# High_Current_Supply.net
KiCad netlist of a schematic drawn in EAGLE
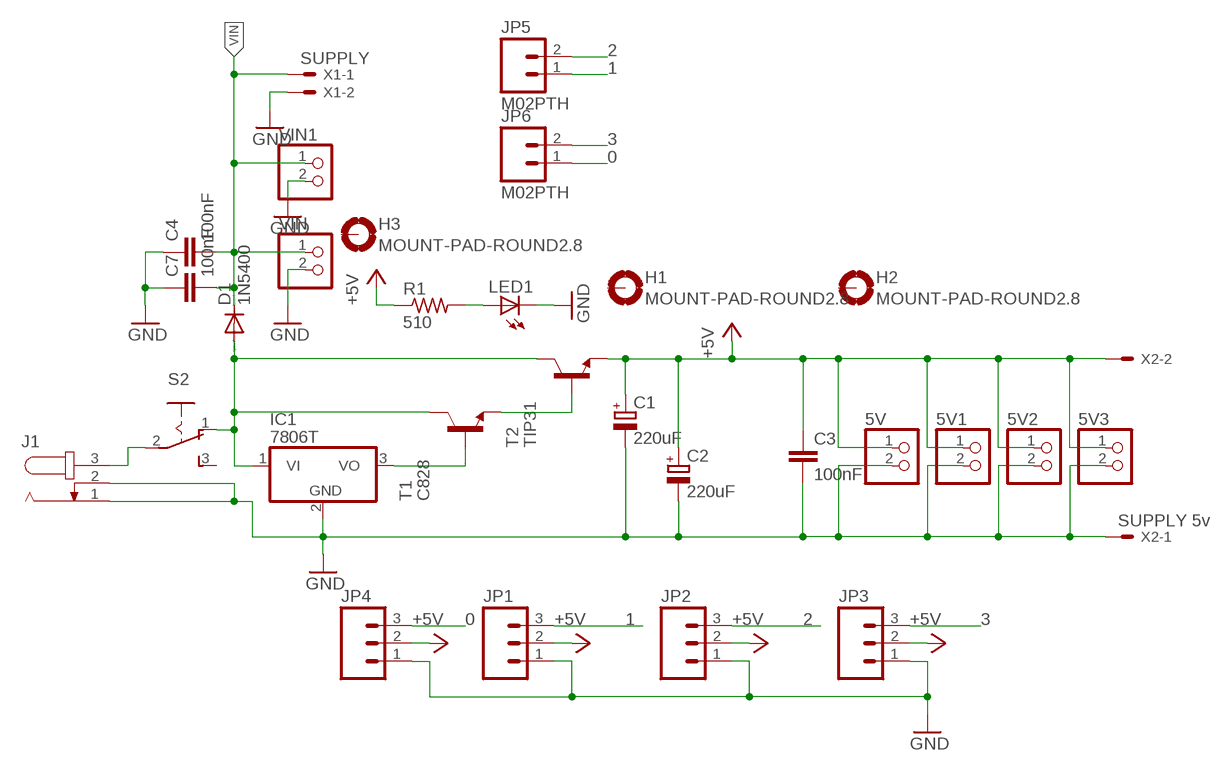
[diagram p0: schematic, sheet 1]

(export (version "E")
  (design (tool "Eeschema 10.0.6"))
  (components
    (comp (ref "5V")
      (value "PINHD-1X2")
      (footprint "eagle-import:1X02")
      (libsource (lib "eagle-import") (part "PINHD-1X2"))
    )
    (comp (ref "5V1")
      (value "PINHD-1X2")
      (footprint "eagle-import:1X02")
      (libsource (lib "eagle-import") (part "PINHD-1X2"))
    )
    (comp (ref "5V2")
      (value "PINHD-1X2")
      (footprint "eagle-import:1X02")
      (libsource (lib "eagle-import") (part "PINHD-1X2"))
    )
    (comp (ref "5V3")
      (value "PINHD-1X2")
      (footprint "eagle-import:1X02")
      (libsource (lib "eagle-import") (part "PINHD-1X2"))
    )
    (comp (ref "C1")
      (value "220uF")
      (footprint "eagle-import:E2,5-7")
      (libsource (lib "eagle-import") (part "CPOL-EUE2.5-7"))
    )
    (comp (ref "C2")
      (value "220uF")
      (footprint "eagle-import:E2,5-7")
      (libsource (lib "eagle-import") (part "CPOL-EUE2.5-7"))
    )
    (comp (ref "C3")
      (value "100nF")
      (footprint "eagle-import:C5B3")
      (libsource (lib "eagle-import") (part "C5/3"))
    )
    (comp (ref "C4")
      (value "100nF")
      (footprint "eagle-import:C5B3")
      (libsource (lib "eagle-import") (part "C5/3"))
    )
    (comp (ref "C7")
      (value "100nF")
      (footprint "eagle-import:C5B3")
      (libsource (lib "eagle-import") (part "C5/3"))
    )
    (comp (ref "D1")
      (value "1N5400")
      (footprint "eagle-import:DO201-15")
      (libsource (lib "eagle-import") (part "1N5400"))
    )
    (comp (ref "H1")
      (value "MOUNT-PAD-ROUND2.8")
      (footprint "eagle-import:2,8-PAD")
      (libsource (lib "eagle-import") (part "MOUNT-PAD-ROUND2.8"))
    )
    (comp (ref "H2")
      (value "MOUNT-PAD-ROUND2.8")
      (footprint "eagle-import:2,8-PAD")
      (libsource (lib "eagle-import") (part "MOUNT-PAD-ROUND2.8"))
    )
    (comp (ref "H3")
      (value "MOUNT-PAD-ROUND2.8")
      (footprint "eagle-import:2,8-PAD")
      (libsource (lib "eagle-import") (part "MOUNT-PAD-ROUND2.8"))
    )
    (comp (ref "IC1")
      (value "7806T")
      (footprint "eagle-import:TO220H")
      (libsource (lib "eagle-import") (part "78T06"))
    )
    (comp (ref "J1")
      (value "JACK-PLUG1")
      (footprint "eagle-import:SPC4078")
      (libsource (lib "eagle-import") (part "JACK-PLUG1"))
    )
    (comp (ref "JP1")
      (value "M03PTH")
      (footprint "eagle-import:1X03")
      (libsource (lib "eagle-import") (part "M03PTH"))
    )
    (comp (ref "JP2")
      (value "M03PTH")
      (footprint "eagle-import:1X03")
      (libsource (lib "eagle-import") (part "M03PTH"))
    )
    (comp (ref "JP3")
      (value "M03PTH")
      (footprint "eagle-import:1X03")
      (libsource (lib "eagle-import") (part "M03PTH"))
    )
    (comp (ref "JP4")
      (value "M03PTH")
      (footprint "eagle-import:1X03")
      (libsource (lib "eagle-import") (part "M03PTH"))
    )
    (comp (ref "JP5")
      (value "M02PTH")
      (footprint "eagle-import:1X02")
      (libsource (lib "eagle-import") (part "M02PTH"))
    )
    (comp (ref "JP6")
      (value "M02PTH")
      (footprint "eagle-import:1X02")
      (libsource (lib "eagle-import") (part "M02PTH"))
    )
    (comp (ref "LED1")
      (value "LED3MM")
      (footprint "eagle-import:LED3MM")
      (libsource (lib "eagle-import") (part "LED3MM"))
    )
    (comp (ref "R1")
      (value "510")
      (footprint "eagle-import:R0603")
      (libsource (lib "eagle-import") (part "R-US_R0603"))
    )
    (comp (ref "S2")
      (value "255SB")
      (footprint "eagle-import:255SB")
      (libsource (lib "eagle-import") (part "255SB"))
    )
    (comp (ref "T1")
      (value "C828")
      (footprint "eagle-import:TO92-ECB")
      (libsource (lib "eagle-import") (part "2SC945"))
    )
    (comp (ref "T2")
      (value "TIP31")
      (footprint "eagle-import:TO220")
      (libsource (lib "eagle-import") (part "TIP31"))
    )
    (comp (ref "VIN")
      (value "PINHD-1X2")
      (footprint "eagle-import:1X02")
      (libsource (lib "eagle-import") (part "PINHD-1X2"))
    )
    (comp (ref "VIN1")
      (value "PINHD-1X2")
      (footprint "eagle-import:1X02")
      (libsource (lib "eagle-import") (part "PINHD-1X2"))
    )
    (comp (ref "X1")
      (value "SUPPLY")
      (footprint "eagle-import:JST-XH-02-PACKAGE-LONG-PAD")
      (libsource (lib "eagle-import") (part "JST-XH-02-PIN-LONG-PAD"))
    )
    (comp (ref "X2")
      (value "SUPPLY 5v")
      (footprint "eagle-import:JST-XH-02-PACKAGE-LONG-PAD")
      (libsource (lib "eagle-import") (part "JST-XH-02-PIN-LONG-PAD"))
    )
  )
  (nets
    (net (code "1") (name "+5V") (class "Default")
      (node (ref "5V") (pin "1") (pinfunction "1_1") (pintype "passive"))
      (node (ref "5V1") (pin "1") (pinfunction "1_1") (pintype "passive"))
      (node (ref "5V2") (pin "1") (pinfunction "1_1") (pintype "passive"))
      (node (ref "5V3") (pin "1") (pinfunction "1_1") (pintype "passive"))
      (node (ref "C1") (pin "+") (pinfunction "+_+") (pintype "passive"))
      (node (ref "C2") (pin "+") (pinfunction "+_+") (pintype "passive"))
      (node (ref "C3") (pin "1") (pinfunction "1_1") (pintype "passive"))
      (node (ref "JP1") (pin "2") (pinfunction "2_2") (pintype "passive"))
      (node (ref "JP2") (pin "2") (pinfunction "2_2") (pintype "passive"))
      (node (ref "JP3") (pin "2") (pinfunction "2_2") (pintype "passive"))
      (node (ref "JP4") (pin "2") (pinfunction "2_2") (pintype "passive"))
      (node (ref "R1") (pin "1") (pinfunction "1_1") (pintype "passive"))
      (node (ref "T2") (pin "3") (pinfunction "E_3") (pintype "passive"))
      (node (ref "X2") (pin "2") (pinfunction "S_2") (pintype "passive"))
    )
    (net (code "2") (name "/0") (class "Default")
      (node (ref "JP4") (pin "3") (pinfunction "3_3") (pintype "passive"))
      (node (ref "JP6") (pin "1") (pinfunction "1_1") (pintype "passive"))
    )
    (net (code "3") (name "/1") (class "Default")
      (node (ref "JP1") (pin "3") (pinfunction "3_3") (pintype "passive"))
      (node (ref "JP5") (pin "1") (pinfunction "1_1") (pintype "passive"))
    )
    (net (code "4") (name "/2") (class "Default")
      (node (ref "JP2") (pin "3") (pinfunction "3_3") (pintype "passive"))
      (node (ref "JP5") (pin "2") (pinfunction "2_2") (pintype "passive"))
    )
    (net (code "5") (name "/3") (class "Default")
      (node (ref "JP3") (pin "3") (pinfunction "3_3") (pintype "passive"))
      (node (ref "JP6") (pin "2") (pinfunction "2_2") (pintype "passive"))
    )
    (net (code "6") (name "GND") (class "Default")
      (node (ref "5V") (pin "2") (pinfunction "2_2") (pintype "passive"))
      (node (ref "5V1") (pin "2") (pinfunction "2_2") (pintype "passive"))
      (node (ref "5V2") (pin "2") (pinfunction "2_2") (pintype "passive"))
      (node (ref "5V3") (pin "2") (pinfunction "2_2") (pintype "passive"))
      (node (ref "C1") (pin "-") (pinfunction "-_-") (pintype "passive"))
      (node (ref "C2") (pin "-") (pinfunction "-_-") (pintype "passive"))
      (node (ref "C3") (pin "2") (pinfunction "2_2") (pintype "passive"))
      (node (ref "C4") (pin "1") (pinfunction "1_1") (pintype "passive"))
      (node (ref "C7") (pin "1") (pinfunction "1_1") (pintype "passive"))
      (node (ref "IC1") (pin "2") (pinfunction "GND_2") (pintype "passive"))
      (node (ref "J1") (pin "1") (pinfunction "1_1") (pintype "passive"))
      (node (ref "J1") (pin "2") (pinfunction "2_2") (pintype "passive"))
      (node (ref "JP1") (pin "1") (pinfunction "1_1") (pintype "passive"))
      (node (ref "JP2") (pin "1") (pinfunction "1_1") (pintype "passive"))
      (node (ref "JP3") (pin "1") (pinfunction "1_1") (pintype "passive"))
      (node (ref "JP4") (pin "1") (pinfunction "1_1") (pintype "passive"))
      (node (ref "LED1") (pin "K") (pinfunction "C_K") (pintype "passive"))
      (node (ref "VIN") (pin "2") (pinfunction "2_2") (pintype "passive"))
      (node (ref "VIN1") (pin "2") (pinfunction "2_2") (pintype "passive"))
      (node (ref "X1") (pin "2") (pinfunction "S_2") (pintype "passive"))
      (node (ref "X2") (pin "1") (pinfunction "S_1") (pintype "passive"))
    )
    (net (code "7") (name "Net-(IC1-VI)") (class "Default")
      (node (ref "D1") (pin "A") (pinfunction "A_A") (pintype "passive"))
      (node (ref "IC1") (pin "1") (pinfunction "VI_1") (pintype "input"))
      (node (ref "S2") (pin "1") (pinfunction "O_1") (pintype "passive"))
      (node (ref "T1") (pin "C") (pinfunction "C_C") (pintype "passive"))
      (node (ref "T2") (pin "2") (pinfunction "C_2") (pintype "passive"))
    )
    (net (code "8") (name "Net-(IC1-VO)") (class "Default")
      (node (ref "IC1") (pin "3") (pinfunction "VO_3") (pintype "passive"))
      (node (ref "T1") (pin "B") (pinfunction "B_B") (pintype "passive"))
    )
    (net (code "9") (name "Net-(LED1-PadA)") (class "Default")
      (node (ref "LED1") (pin "A") (pinfunction "A_A") (pintype "passive"))
      (node (ref "R1") (pin "2") (pinfunction "2_2") (pintype "passive"))
    )
    (net (code "10") (name "Net-(S2-P)") (class "Default")
      (node (ref "J1") (pin "3") (pinfunction "3_3") (pintype "passive"))
      (node (ref "S2") (pin "2") (pinfunction "P_2") (pintype "passive"))
    )
    (net (code "11") (name "Net-(T2-B)") (class "Default")
      (node (ref "T1") (pin "E") (pinfunction "E_E") (pintype "passive"))
      (node (ref "T2") (pin "1") (pinfunction "B_1") (pintype "passive"))
    )
    (net (code "12") (name "VIN") (class "Default")
      (node (ref "C4") (pin "2") (pinfunction "2_2") (pintype "passive"))
      (node (ref "C7") (pin "2") (pinfunction "2_2") (pintype "passive"))
      (node (ref "D1") (pin "C") (pinfunction "C_C") (pintype "passive"))
      (node (ref "VIN") (pin "1") (pinfunction "1_1") (pintype "passive"))
      (node (ref "VIN1") (pin "1") (pinfunction "1_1") (pintype "passive"))
      (node (ref "X1") (pin "1") (pinfunction "S_1") (pintype "passive"))
    )
    (net (code "13") (name "unconnected-(H1-MOUNT-PadB2,8)") (class "Default")
      (node (ref "H1") (pin "B2,8") (pinfunction "MOUNT_B2,8") (pintype "passive"))
    )
    (net (code "14") (name "unconnected-(H2-MOUNT-PadB2,8)") (class "Default")
      (node (ref "H2") (pin "B2,8") (pinfunction "MOUNT_B2,8") (pintype "passive"))
    )
    (net (code "15") (name "unconnected-(H3-MOUNT-PadB2,8)") (class "Default")
      (node (ref "H3") (pin "B2,8") (pinfunction "MOUNT_B2,8") (pintype "passive"))
    )
    (net (code "16") (name "unconnected-(S2-S-Pad3)") (class "Default")
      (node (ref "S2") (pin "3") (pinfunction "S_3") (pintype "passive"))
    )
  )
)
